# robotarm.net
KiCad netlist of a schematic drawn in EAGLE
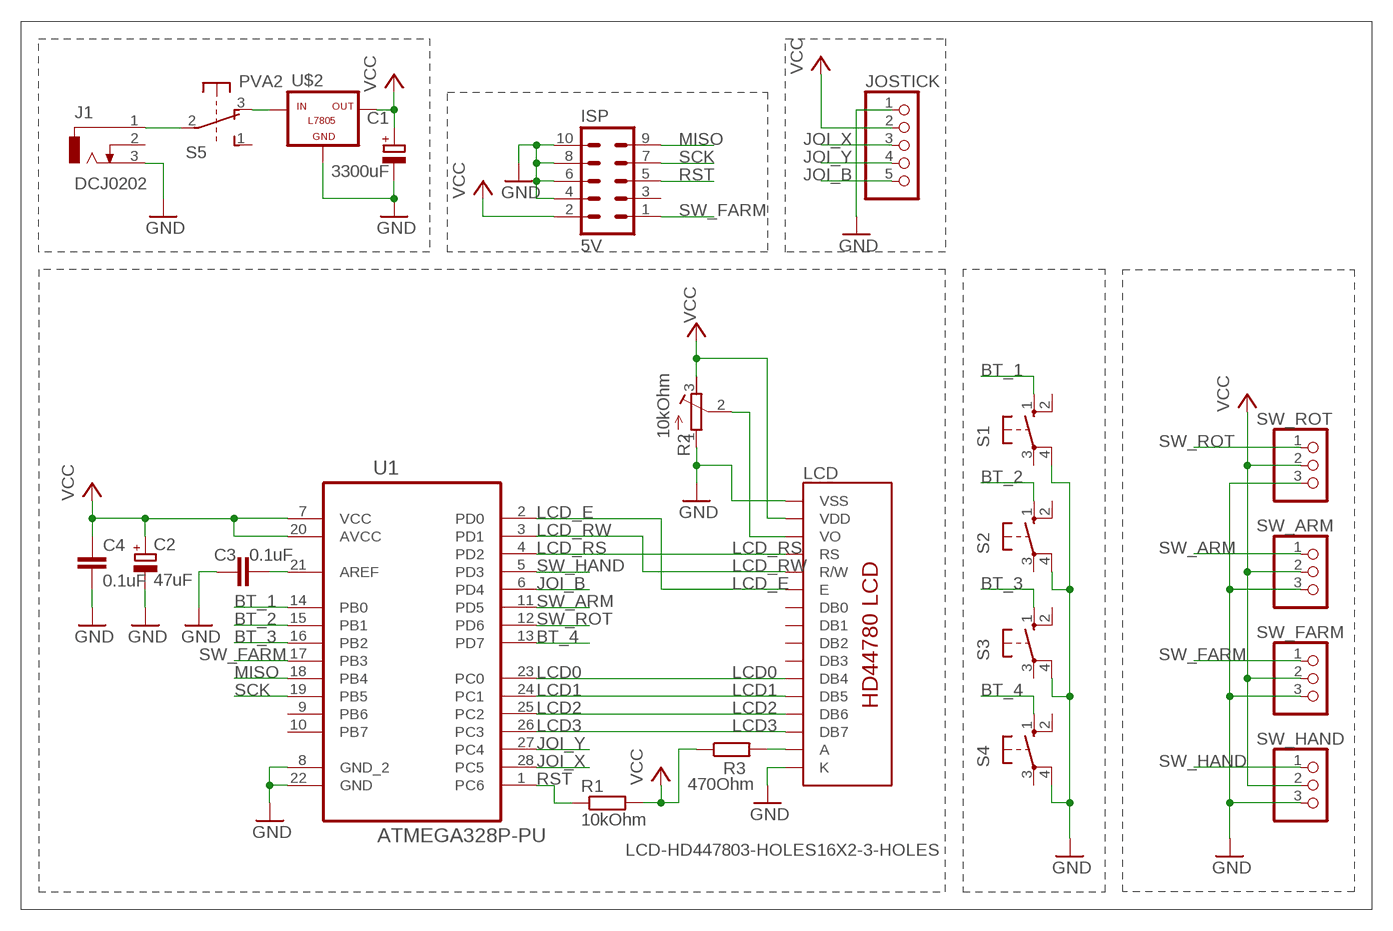
[diagram p0: schematic, sheet 1]

(export (version "E")
  (design (tool "Eeschema 10.0.6"))
  (components
    (comp (ref "C1")
      (value "3300uF")
      (footprint "eagle-import:E3,5-10")
      (libsource (lib "eagle-import") (part "CPOL-EUE3.5-10"))
    )
    (comp (ref "C2")
      (value "47uF")
      (footprint "eagle-import:E2,5-6")
      (libsource (lib "eagle-import") (part "CPOL-EUE2.5-6"))
    )
    (comp (ref "C3")
      (value "0.1uF")
      (footprint "eagle-import:C025-024X044")
      (libsource (lib "eagle-import") (part "C-EU025-024X044"))
    )
    (comp (ref "C4")
      (value "0.1uF")
      (footprint "eagle-import:C025-024X044")
      (libsource (lib "eagle-import") (part "C-EU025-024X044"))
    )
    (comp (ref "ISP")
      (value "5V")
      (footprint "eagle-import:ML10")
      (libsource (lib "eagle-import") (part "ML10"))
    )
    (comp (ref "J1")
      (value "DCJ0202")
      (footprint "eagle-import:DCJ0202")
      (libsource (lib "eagle-import") (part "DCJ0202"))
    )
    (comp (ref "JOSTICK")
      (value "PINHD-1X5")
      (footprint "eagle-import:1X05")
      (libsource (lib "eagle-import") (part "PINHD-1X5"))
    )
    (comp (ref "LCD")
      (value "LCD-HD447803-HOLES16X2-3-HOLES")
      (footprint "eagle-import:LCD-16X2-3HOLES")
      (libsource (lib "eagle-import") (part "LCD-HD4478016X2-3-HOLES3-HOLES"))
    )
    (comp (ref "R1")
      (value "10kOhm")
      (footprint "eagle-import:0204_7")
      (libsource (lib "eagle-import") (part "R-EU_0204/7"))
    )
    (comp (ref "R2")
      (value "10kOhm")
      (footprint "eagle-import:RTRIM3339P")
      (libsource (lib "eagle-import") (part "R-TRIMM3339P"))
    )
    (comp (ref "R3")
      (value "470Ohm")
      (footprint "eagle-import:0204_7")
      (libsource (lib "eagle-import") (part "R-EU_0204/7"))
    )
    (comp (ref "S1")
      (value "10-XX")
      (footprint "eagle-import:B3F-10XX")
      (fields (field (name "MPN") "B3F-1000"))
      (libsource (lib "eagle-import") (part "10-XX"))
    )
    (comp (ref "S2")
      (value "10-XX")
      (footprint "eagle-import:B3F-10XX")
      (fields (field (name "MPN") "B3F-1000"))
      (libsource (lib "eagle-import") (part "10-XX"))
    )
    (comp (ref "S3")
      (value "10-XX")
      (footprint "eagle-import:B3F-10XX")
      (fields (field (name "MPN") "B3F-1000"))
      (libsource (lib "eagle-import") (part "10-XX"))
    )
    (comp (ref "S4")
      (value "10-XX")
      (footprint "eagle-import:B3F-10XX")
      (fields (field (name "MPN") "B3F-1000"))
      (libsource (lib "eagle-import") (part "10-XX"))
    )
    (comp (ref "S5")
      (value "PVA2")
      (footprint "eagle-import:PVA2F")
      (libsource (lib "eagle-import") (part "PVA2"))
    )
    (comp (ref "SW_ARM")
      (value "PINHD-1X3")
      (footprint "eagle-import:1X03")
      (libsource (lib "eagle-import") (part "PINHD-1X3"))
    )
    (comp (ref "SW_FARM")
      (value "PINHD-1X3")
      (footprint "eagle-import:1X03")
      (libsource (lib "eagle-import") (part "PINHD-1X3"))
    )
    (comp (ref "SW_HAND")
      (value "PINHD-1X3")
      (footprint "eagle-import:1X03")
      (libsource (lib "eagle-import") (part "PINHD-1X3"))
    )
    (comp (ref "SW_ROT")
      (value "PINHD-1X3")
      (footprint "eagle-import:1X03")
      (libsource (lib "eagle-import") (part "PINHD-1X3"))
    )
    (comp (ref "U$2")
      (value "-L7805")
      (footprint "eagle-import:L7805")
      (libsource (lib "eagle-import") (part "-L7805"))
    )
    (comp (ref "U1")
      (value "ATMEGA328P-PU")
      (footprint "eagle-import:DIP254P762X457-28")
      (libsource (lib "eagle-import") (part "ATMEGA328P-PU"))
    )
  )
  (nets
    (net (code "1") (name "/BT_1") (class "Default")
      (node (ref "S1") (pin "1") (pinfunction "S_1") (pintype "passive"))
      (node (ref "U1") (pin "14") (pinfunction "PB0_14") (pintype "bidirectional"))
    )
    (net (code "2") (name "/BT_2") (class "Default")
      (node (ref "S2") (pin "1") (pinfunction "S_1") (pintype "passive"))
      (node (ref "U1") (pin "15") (pinfunction "PB1_15") (pintype "bidirectional"))
    )
    (net (code "3") (name "/BT_3") (class "Default")
      (node (ref "S3") (pin "1") (pinfunction "S_1") (pintype "passive"))
      (node (ref "U1") (pin "16") (pinfunction "PB2_16") (pintype "bidirectional"))
    )
    (net (code "4") (name "/BT_4") (class "Default")
      (node (ref "S4") (pin "1") (pinfunction "S_1") (pintype "passive"))
      (node (ref "U1") (pin "13") (pinfunction "PD7_13") (pintype "bidirectional"))
    )
    (net (code "5") (name "/JOI_B") (class "Default")
      (node (ref "JOSTICK") (pin "5") (pinfunction "5_5") (pintype "passive"))
      (node (ref "U1") (pin "6") (pinfunction "PD4_6") (pintype "bidirectional"))
    )
    (net (code "6") (name "/JOI_X") (class "Default")
      (node (ref "JOSTICK") (pin "3") (pinfunction "3_3") (pintype "passive"))
      (node (ref "U1") (pin "28") (pinfunction "PC5_28") (pintype "bidirectional"))
    )
    (net (code "7") (name "/JOI_Y") (class "Default")
      (node (ref "JOSTICK") (pin "4") (pinfunction "4_4") (pintype "passive"))
      (node (ref "U1") (pin "27") (pinfunction "PC4_27") (pintype "bidirectional"))
    )
    (net (code "8") (name "/LCD0") (class "Default")
      (node (ref "LCD") (pin "11") (pinfunction "DB4_11") (pintype "bidirectional"))
      (node (ref "U1") (pin "23") (pinfunction "PC0_23") (pintype "bidirectional"))
    )
    (net (code "9") (name "/LCD1") (class "Default")
      (node (ref "LCD") (pin "12") (pinfunction "DB5_12") (pintype "bidirectional"))
      (node (ref "U1") (pin "24") (pinfunction "PC1_24") (pintype "bidirectional"))
    )
    (net (code "10") (name "/LCD2") (class "Default")
      (node (ref "LCD") (pin "13") (pinfunction "DB6_13") (pintype "bidirectional"))
      (node (ref "U1") (pin "25") (pinfunction "PC2_25") (pintype "bidirectional"))
    )
    (net (code "11") (name "/LCD3") (class "Default")
      (node (ref "LCD") (pin "14") (pinfunction "DB7_14") (pintype "bidirectional"))
      (node (ref "U1") (pin "26") (pinfunction "PC3_26") (pintype "bidirectional"))
    )
    (net (code "12") (name "/LCD_E") (class "Default")
      (node (ref "LCD") (pin "6") (pinfunction "E_6") (pintype "input"))
      (node (ref "U1") (pin "2") (pinfunction "PD0_2") (pintype "bidirectional"))
    )
    (net (code "13") (name "/LCD_RS") (class "Default")
      (node (ref "LCD") (pin "4") (pinfunction "RS_4") (pintype "input"))
      (node (ref "U1") (pin "4") (pinfunction "PD2_4") (pintype "bidirectional"))
    )
    (net (code "14") (name "/LCD_RW") (class "Default")
      (node (ref "LCD") (pin "5") (pinfunction "R/W_5") (pintype "input"))
      (node (ref "U1") (pin "3") (pinfunction "PD1_3") (pintype "bidirectional"))
    )
    (net (code "15") (name "/MISO") (class "Default")
      (node (ref "ISP") (pin "9") (pinfunction "9_9") (pintype "passive"))
      (node (ref "U1") (pin "18") (pinfunction "PB4_18") (pintype "bidirectional"))
    )
    (net (code "16") (name "/RST") (class "Default")
      (node (ref "ISP") (pin "5") (pinfunction "5_5") (pintype "passive"))
      (node (ref "R1") (pin "1") (pinfunction "1_1") (pintype "passive"))
      (node (ref "U1") (pin "1") (pinfunction "PC6_1") (pintype "bidirectional"))
    )
    (net (code "17") (name "/SCK") (class "Default")
      (node (ref "ISP") (pin "7") (pinfunction "7_7") (pintype "passive"))
      (node (ref "U1") (pin "19") (pinfunction "PB5_19") (pintype "bidirectional"))
    )
    (net (code "18") (name "/SW_ARM") (class "Default")
      (node (ref "SW_ARM") (pin "1") (pinfunction "1_1") (pintype "passive"))
      (node (ref "U1") (pin "11") (pinfunction "PD5_11") (pintype "bidirectional"))
    )
    (net (code "19") (name "/SW_FARM") (class "Default")
      (node (ref "ISP") (pin "1") (pinfunction "1_1") (pintype "passive"))
      (node (ref "SW_FARM") (pin "1") (pinfunction "1_1") (pintype "passive"))
      (node (ref "U1") (pin "17") (pinfunction "PB3_17") (pintype "bidirectional"))
    )
    (net (code "20") (name "/SW_HAND") (class "Default")
      (node (ref "SW_HAND") (pin "1") (pinfunction "1_1") (pintype "passive"))
      (node (ref "U1") (pin "5") (pinfunction "PD3_5") (pintype "bidirectional"))
    )
    (net (code "21") (name "/SW_ROT") (class "Default")
      (node (ref "SW_ROT") (pin "1") (pinfunction "1_1") (pintype "passive"))
      (node (ref "U1") (pin "12") (pinfunction "PD6_12") (pintype "bidirectional"))
    )
    (net (code "22") (name "GND") (class "Default")
      (node (ref "C1") (pin "-") (pinfunction "-_-") (pintype "passive"))
      (node (ref "C2") (pin "-") (pinfunction "-_-") (pintype "passive"))
      (node (ref "C3") (pin "1") (pinfunction "1_1") (pintype "passive"))
      (node (ref "C4") (pin "2") (pinfunction "2_2") (pintype "passive"))
      (node (ref "ISP") (pin "10") (pinfunction "10_10") (pintype "passive"))
      (node (ref "ISP") (pin "4") (pinfunction "4_4") (pintype "passive"))
      (node (ref "ISP") (pin "6") (pinfunction "6_6") (pintype "passive"))
      (node (ref "ISP") (pin "8") (pinfunction "8_8") (pintype "passive"))
      (node (ref "J1") (pin "3") (pinfunction "3_3") (pintype "passive"))
      (node (ref "JOSTICK") (pin "1") (pinfunction "1_1") (pintype "passive"))
      (node (ref "LCD") (pin "1") (pinfunction "VSS_1") (pintype "power_in"))
      (node (ref "LCD") (pin "16") (pinfunction "K_16") (pintype "power_in"))
      (node (ref "R2") (pin "1") (pinfunction "A_1") (pintype "passive"))
      (node (ref "S1") (pin "4") (pinfunction "P1_4") (pintype "passive"))
      (node (ref "S2") (pin "4") (pinfunction "P1_4") (pintype "passive"))
      (node (ref "S3") (pin "4") (pinfunction "P1_4") (pintype "passive"))
      (node (ref "S4") (pin "4") (pinfunction "P1_4") (pintype "passive"))
      (node (ref "SW_ARM") (pin "3") (pinfunction "3_3") (pintype "passive"))
      (node (ref "SW_FARM") (pin "3") (pinfunction "3_3") (pintype "passive"))
      (node (ref "SW_HAND") (pin "3") (pinfunction "3_3") (pintype "passive"))
      (node (ref "SW_ROT") (pin "3") (pinfunction "3_3") (pintype "passive"))
      (node (ref "U$2") (pin "GND") (pinfunction "GND_GND") (pintype "input"))
      (node (ref "U1") (pin "22") (pinfunction "GND_22") (pintype "passive"))
      (node (ref "U1") (pin "8") (pinfunction "GND_2_8") (pintype "passive"))
    )
    (net (code "23") (name "Net-(LCD-A)") (class "Default")
      (node (ref "LCD") (pin "15") (pinfunction "A_15") (pintype "power_in"))
      (node (ref "R3") (pin "2") (pinfunction "2_2") (pintype "passive"))
    )
    (net (code "24") (name "Net-(LCD-VO)") (class "Default")
      (node (ref "LCD") (pin "3") (pinfunction "VO_3") (pintype "bidirectional"))
      (node (ref "R2") (pin "2") (pinfunction "S_2") (pintype "passive"))
    )
    (net (code "25") (name "Net-(S5A-O)") (class "Default")
      (node (ref "S5") (pin "3") (pinfunction "O_3") (pintype "passive"))
      (node (ref "U$2") (pin "IN") (pinfunction "IN_IN") (pintype "input"))
    )
    (net (code "26") (name "Net-(S5A-P)") (class "Default")
      (node (ref "J1") (pin "1") (pinfunction "1_1") (pintype "passive"))
      (node (ref "S5") (pin "2") (pinfunction "P_2") (pintype "passive"))
    )
    (net (code "27") (name "Net-(U1-AREF)") (class "Default")
      (node (ref "C3") (pin "2") (pinfunction "2_2") (pintype "passive"))
      (node (ref "U1") (pin "21") (pinfunction "AREF_21") (pintype "input"))
    )
    (net (code "28") (name "VCC") (class "Default")
      (node (ref "C1") (pin "+") (pinfunction "+_+") (pintype "passive"))
      (node (ref "C2") (pin "+") (pinfunction "+_+") (pintype "passive"))
      (node (ref "C4") (pin "1") (pinfunction "1_1") (pintype "passive"))
      (node (ref "ISP") (pin "2") (pinfunction "2_2") (pintype "passive"))
      (node (ref "JOSTICK") (pin "2") (pinfunction "2_2") (pintype "passive"))
      (node (ref "LCD") (pin "2") (pinfunction "VDD_2") (pintype "power_in"))
      (node (ref "R1") (pin "2") (pinfunction "2_2") (pintype "passive"))
      (node (ref "R2") (pin "3") (pinfunction "E_3") (pintype "passive"))
      (node (ref "R3") (pin "1") (pinfunction "1_1") (pintype "passive"))
      (node (ref "SW_ARM") (pin "2") (pinfunction "2_2") (pintype "passive"))
      (node (ref "SW_FARM") (pin "2") (pinfunction "2_2") (pintype "passive"))
      (node (ref "SW_HAND") (pin "2") (pinfunction "2_2") (pintype "passive"))
      (node (ref "SW_ROT") (pin "2") (pinfunction "2_2") (pintype "passive"))
      (node (ref "U$2") (pin "OUT") (pinfunction "OUT_OUT") (pintype "passive"))
      (node (ref "U1") (pin "20") (pinfunction "AVCC_20") (pintype "power_in"))
      (node (ref "U1") (pin "7") (pinfunction "VCC_7") (pintype "power_in"))
    )
    (net (code "29") (name "unconnected-(ISP-Pad3)") (class "Default")
      (node (ref "ISP") (pin "3") (pinfunction "3_3") (pintype "passive"))
    )
    (net (code "30") (name "unconnected-(J1-Pad2)") (class "Default")
      (node (ref "J1") (pin "2") (pinfunction "2_2") (pintype "passive"))
    )
    (net (code "31") (name "unconnected-(LCD-DB0-Pad7)") (class "Default")
      (node (ref "LCD") (pin "7") (pinfunction "DB0_7") (pintype "bidirectional"))
    )
    (net (code "32") (name "unconnected-(LCD-DB1-Pad8)") (class "Default")
      (node (ref "LCD") (pin "8") (pinfunction "DB1_8") (pintype "bidirectional"))
    )
    (net (code "33") (name "unconnected-(LCD-DB2-Pad9)") (class "Default")
      (node (ref "LCD") (pin "9") (pinfunction "DB2_9") (pintype "bidirectional"))
    )
    (net (code "34") (name "unconnected-(LCD-DB3-Pad10)") (class "Default")
      (node (ref "LCD") (pin "10") (pinfunction "DB3_10") (pintype "bidirectional"))
    )
    (net (code "35") (name "unconnected-(S1-P-Pad3)") (class "Default")
      (node (ref "S1") (pin "3") (pinfunction "P_3") (pintype "passive"))
    )
    (net (code "36") (name "unconnected-(S1-S1-Pad2)") (class "Default")
      (node (ref "S1") (pin "2") (pinfunction "S1_2") (pintype "passive"))
    )
    (net (code "37") (name "unconnected-(S2-P-Pad3)") (class "Default")
      (node (ref "S2") (pin "3") (pinfunction "P_3") (pintype "passive"))
    )
    (net (code "38") (name "unconnected-(S2-S1-Pad2)") (class "Default")
      (node (ref "S2") (pin "2") (pinfunction "S1_2") (pintype "passive"))
    )
    (net (code "39") (name "unconnected-(S3-P-Pad3)") (class "Default")
      (node (ref "S3") (pin "3") (pinfunction "P_3") (pintype "passive"))
    )
    (net (code "40") (name "unconnected-(S3-S1-Pad2)") (class "Default")
      (node (ref "S3") (pin "2") (pinfunction "S1_2") (pintype "passive"))
    )
    (net (code "41") (name "unconnected-(S4-P-Pad3)") (class "Default")
      (node (ref "S4") (pin "3") (pinfunction "P_3") (pintype "passive"))
    )
    (net (code "42") (name "unconnected-(S4-S1-Pad2)") (class "Default")
      (node (ref "S4") (pin "2") (pinfunction "S1_2") (pintype "passive"))
    )
    (net (code "43") (name "unconnected-(S5A-S-Pad1)") (class "Default")
      (node (ref "S5") (pin "1") (pinfunction "S_1") (pintype "passive"))
    )
    (net (code "44") (name "unconnected-(U1-PB6-Pad9)") (class "Default")
      (node (ref "U1") (pin "9") (pinfunction "PB6_9") (pintype "bidirectional"))
    )
    (net (code "45") (name "unconnected-(U1-PB7-Pad10)") (class "Default")
      (node (ref "U1") (pin "10") (pinfunction "PB7_10") (pintype "bidirectional"))
    )
  )
)
